# Sheet1.net
KiCad netlist of a schematic drawn in Altium Designer
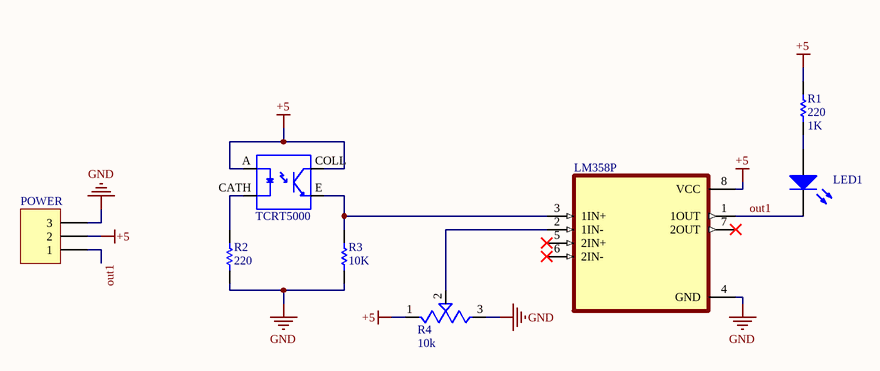
[diagram p0: Sheet1.SchDoc]

(export (version "E")
  (design (tool "Eeschema 10.0.6"))
  (components
    (comp (ref "LED1")
      (value "151031SS06000")
      (footprint "WL-TIRW_D3.9H5.3")
      (description "THT LED round mono-color color lens, WL-TMRW, Super Red")
      (fields (field (name "MANUFACTURER") "Wuerth Elektronik"))
      (libsource (lib "led") (part "CMP-1488-00002-1"))
    )
    (comp (ref "LM358P")
      (value "~")
      (footprint "DIP794W45P254L959H508Q8")
      (description "Dual Operational Amplifiers")
      (fields (field (name "MP") "LM358P") (field (name "MF") "Texas Instruments"))
      (libsource (lib "LM358P") (part "LM358P"))
    )
    (comp (ref "POWER")
      (value "~")
      (footprint "HDR1X3")
      (description "Header, 3-Pin")
      (fields (field (name "PUBLISHER") "Altium Limited"))
      (libsource (lib "Miscellaneous Connectors") (part "Header 3"))
    )
    (comp (ref "R1")
      (value "220")
      (footprint "AXIAL-0.3")
      (description "Resistor")
      (fields (field (name "ALTIUM_VALUE") "1K") (field (name "PUBLISHER") "Altium Limited"))
      (libsource (lib "Miscellaneous Devices") (part "Res1"))
    )
    (comp (ref "R2")
      (value "220")
      (footprint "AXIAL-0.3")
      (description "Resistor")
      (fields (field (name "PUBLISHER") "Altium Limited"))
      (libsource (lib "Miscellaneous Devices") (part "Res1"))
    )
    (comp (ref "R3")
      (value "10K")
      (footprint "AXIAL-0.3")
      (description "Resistor")
      (fields (field (name "PUBLISHER") "Altium Limited"))
      (libsource (lib "Miscellaneous Devices") (part "Res1"))
    )
    (comp (ref "R4")
      (value "10k")
      (footprint "TRIM_3306F-1-203")
      (description "20 kOhms 0.2W")
      (fields (field (name "MP") "3306F-1-203") (field (name "MF") "Bourns"))
      (libsource (lib "3306F-1-203") (part "3306F-1-203"))
    )
    (comp (ref "TCRT5000")
      (value "~")
      (footprint "OPTO_TCRT5000")
      (description "Reflective Optical Sensor 0.591 _15mm_ PCB Mount")
      (fields (field (name "MF") "Vishay") (field (name "MP") "TCRT5000"))
      (libsource (lib "TCRT5000") (part "TCRT5000"))
    )
  )
  (nets
    (net (code "1") (name "+5") (class "Default")
      (node (ref "LM358P") (pin "8") (pinfunction "VCC_8") (pintype "power_in"))
      (node (ref "POWER") (pin "2") (pinfunction "2_2") (pintype "passive"))
      (node (ref "R1") (pin "2") (pinfunction "2_2") (pintype "passive"))
      (node (ref "R4") (pin "1") (pinfunction "CCW_1") (pintype "passive"))
      (node (ref "TCRT5000") (pin "A") (pinfunction "A_A") (pintype "passive"))
      (node (ref "TCRT5000") (pin "COLL") (pinfunction "COLL_COLL") (pintype "passive"))
    )
    (net (code "2") (name "/out1") (class "Default")
      (node (ref "LED1") (pin "1") (pinfunction "K_1") (pintype "passive"))
      (node (ref "LM358P") (pin "1") (pinfunction "1OUT_1") (pintype "output"))
      (node (ref "POWER") (pin "1") (pinfunction "1_1") (pintype "passive"))
    )
    (net (code "3") (name "GND") (class "Default")
      (node (ref "LM358P") (pin "4") (pinfunction "GND_4") (pintype "power_in"))
      (node (ref "POWER") (pin "3") (pinfunction "3_3") (pintype "passive"))
      (node (ref "R2") (pin "1") (pinfunction "1_1") (pintype "passive"))
      (node (ref "R3") (pin "1") (pinfunction "1_1") (pintype "passive"))
      (node (ref "R4") (pin "3") (pinfunction "CW_3") (pintype "passive"))
    )
    (net (code "4") (name "Net-(LED1-A)") (class "Default")
      (node (ref "LED1") (pin "2") (pinfunction "A_2") (pintype "passive"))
      (node (ref "R1") (pin "1") (pinfunction "1_1") (pintype "passive"))
    )
    (net (code "5") (name "Net-(LM358P-1IN+)") (class "Default")
      (node (ref "LM358P") (pin "3") (pinfunction "1IN+_3") (pintype "input"))
      (node (ref "R3") (pin "2") (pinfunction "2_2") (pintype "passive"))
      (node (ref "TCRT5000") (pin "E") (pinfunction "E_E") (pintype "passive"))
    )
    (net (code "6") (name "Net-(LM358P-1IN-)") (class "Default")
      (node (ref "LM358P") (pin "2") (pinfunction "1IN-_2") (pintype "input"))
      (node (ref "R4") (pin "2") (pinfunction "W_2") (pintype "passive"))
    )
    (net (code "7") (name "Net-(R2-Pad2)") (class "Default")
      (node (ref "R2") (pin "2") (pinfunction "2_2") (pintype "passive"))
      (node (ref "TCRT5000") (pin "CATH") (pinfunction "CATH_CATH") (pintype "passive"))
    )
    (net (code "8") (name "unconnected-(LM358P-2IN+-Pad5)") (class "Default")
      (node (ref "LM358P") (pin "5") (pinfunction "2IN+_5") (pintype "input+no_connect"))
    )
    (net (code "9") (name "unconnected-(LM358P-2IN--Pad6)") (class "Default")
      (node (ref "LM358P") (pin "6") (pinfunction "2IN-_6") (pintype "input+no_connect"))
    )
    (net (code "10") (name "unconnected-(LM358P-2OUT-Pad7)") (class "Default")
      (node (ref "LM358P") (pin "7") (pinfunction "2OUT_7") (pintype "output+no_connect"))
    )
  )
)
